# Main_circuit_SMD.net
KiCad netlist of a schematic drawn in EAGLE
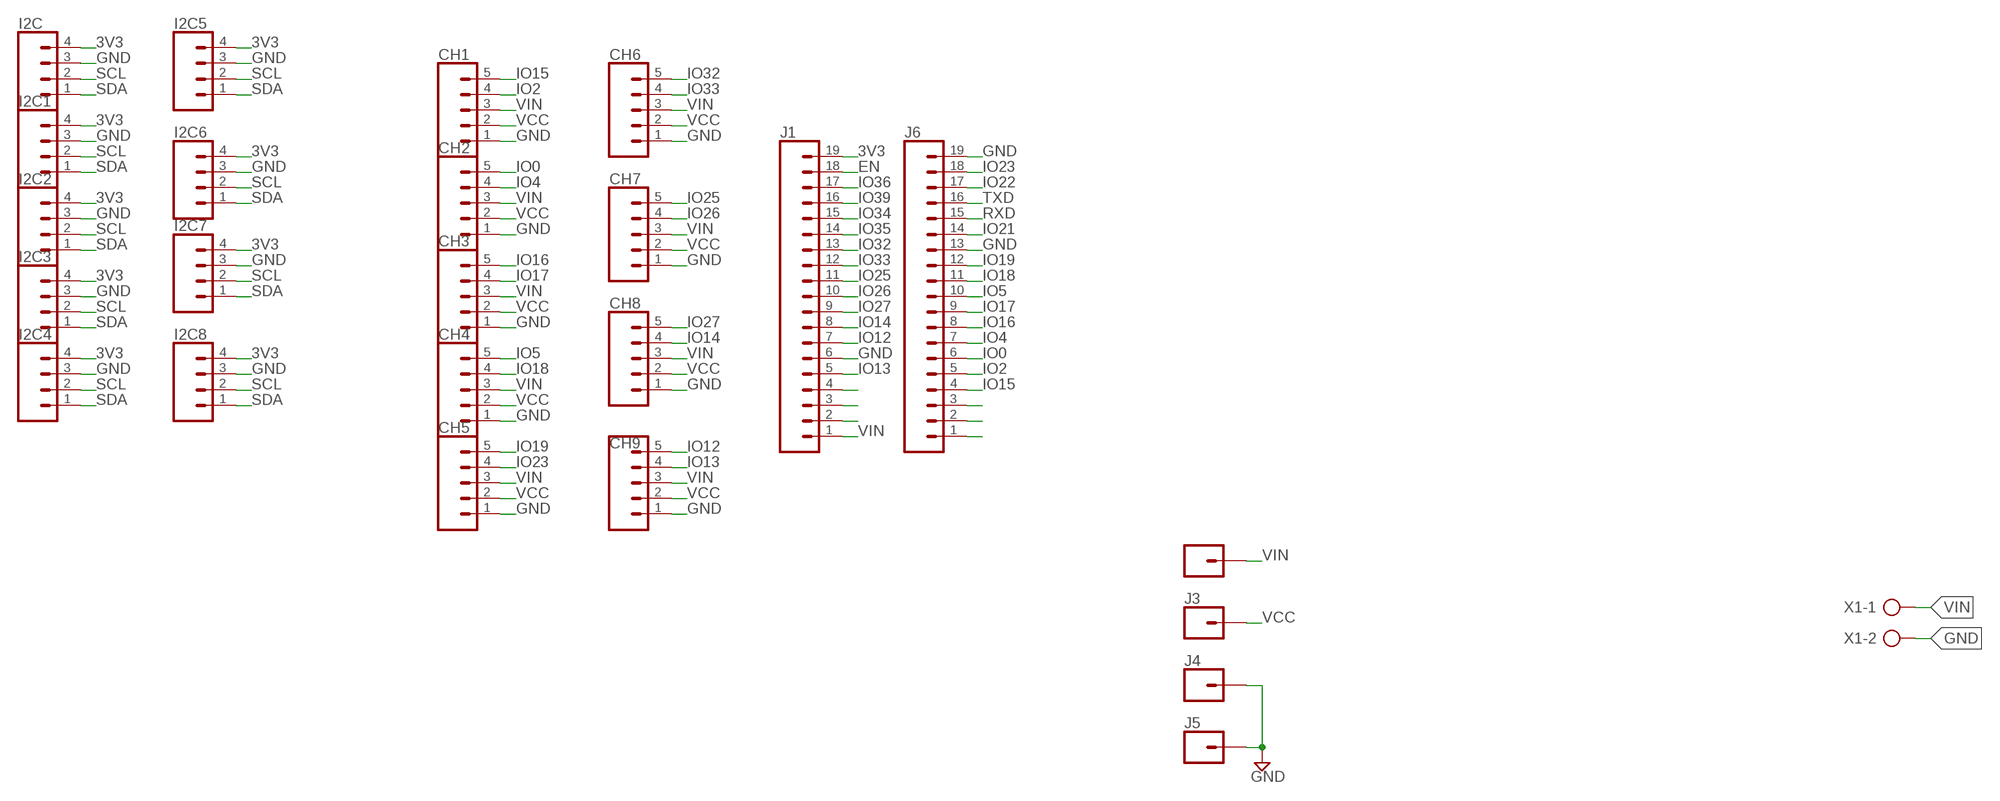
[diagram p0: schematic, sheet 1]

(export (version "E")
  (design (tool "Eeschema 10.0.6"))
  (components
    (comp (ref "CH1")
      (value "CONN_05")
      (footprint "eagle-import:1X05")
      (libsource (lib "eagle-import") (part "CONN_05"))
    )
    (comp (ref "CH2")
      (value "CONN_05")
      (footprint "eagle-import:1X05")
      (libsource (lib "eagle-import") (part "CONN_05"))
    )
    (comp (ref "CH3")
      (value "CONN_05")
      (footprint "eagle-import:1X05")
      (libsource (lib "eagle-import") (part "CONN_05"))
    )
    (comp (ref "CH4")
      (value "CONN_05")
      (footprint "eagle-import:1X05")
      (libsource (lib "eagle-import") (part "CONN_05"))
    )
    (comp (ref "CH5")
      (value "CONN_05")
      (footprint "eagle-import:1X05")
      (libsource (lib "eagle-import") (part "CONN_05"))
    )
    (comp (ref "CH6")
      (value "CONN_05")
      (footprint "eagle-import:1X05")
      (libsource (lib "eagle-import") (part "CONN_05"))
    )
    (comp (ref "CH7")
      (value "CONN_05")
      (footprint "eagle-import:1X05")
      (libsource (lib "eagle-import") (part "CONN_05"))
    )
    (comp (ref "CH8")
      (value "CONN_05")
      (footprint "eagle-import:1X05")
      (libsource (lib "eagle-import") (part "CONN_05"))
    )
    (comp (ref "CH9")
      (value "CONN_05")
      (footprint "eagle-import:1X05")
      (libsource (lib "eagle-import") (part "CONN_05"))
    )
    (comp (ref "I2C")
      (value "CONN_04")
      (footprint "eagle-import:1X04")
      (libsource (lib "eagle-import") (part "CONN_04"))
    )
    (comp (ref "I2C1")
      (value "CONN_04")
      (footprint "eagle-import:1X04")
      (libsource (lib "eagle-import") (part "CONN_04"))
    )
    (comp (ref "I2C2")
      (value "CONN_04")
      (footprint "eagle-import:1X04")
      (libsource (lib "eagle-import") (part "CONN_04"))
    )
    (comp (ref "I2C3")
      (value "CONN_04")
      (footprint "eagle-import:1X04")
      (libsource (lib "eagle-import") (part "CONN_04"))
    )
    (comp (ref "I2C4")
      (value "CONN_04")
      (footprint "eagle-import:1X04")
      (libsource (lib "eagle-import") (part "CONN_04"))
    )
    (comp (ref "I2C5")
      (value "CONN_04")
      (footprint "eagle-import:1X04")
      (libsource (lib "eagle-import") (part "CONN_04"))
    )
    (comp (ref "I2C6")
      (value "CONN_04")
      (footprint "eagle-import:1X04")
      (libsource (lib "eagle-import") (part "CONN_04"))
    )
    (comp (ref "I2C7")
      (value "CONN_04")
      (footprint "eagle-import:1X04")
      (libsource (lib "eagle-import") (part "CONN_04"))
    )
    (comp (ref "I2C8")
      (value "CONN_04")
      (footprint "eagle-import:1X04")
      (libsource (lib "eagle-import") (part "CONN_04"))
    )
    (comp (ref "J1")
      (value "CONN_19")
      (footprint "eagle-import:1X19")
      (libsource (lib "eagle-import") (part "CONN_19"))
    )
    (comp (ref "J2")
      (value "CONN_01")
      (footprint "eagle-import:1X01")
      (libsource (lib "eagle-import") (part "CONN_01"))
    )
    (comp (ref "J3")
      (value "CONN_01")
      (footprint "eagle-import:1X01")
      (libsource (lib "eagle-import") (part "CONN_01"))
    )
    (comp (ref "J4")
      (value "CONN_01")
      (footprint "eagle-import:1X01")
      (libsource (lib "eagle-import") (part "CONN_01"))
    )
    (comp (ref "J5")
      (value "CONN_01")
      (footprint "eagle-import:1X01")
      (libsource (lib "eagle-import") (part "CONN_01"))
    )
    (comp (ref "J6")
      (value "CONN_19")
      (footprint "eagle-import:1X19")
      (libsource (lib "eagle-import") (part "CONN_19"))
    )
    (comp (ref "X1")
      (value "AK500/2-H")
      (footprint "eagle-import:AK500_2-H")
      (libsource (lib "eagle-import") (part "AK500/2-H"))
    )
  )
  (nets
    (net (code "1") (name "/3V3") (class "Default")
      (node (ref "I2C") (pin "4") (pinfunction "4_4") (pintype "passive"))
      (node (ref "I2C1") (pin "4") (pinfunction "4_4") (pintype "passive"))
      (node (ref "I2C2") (pin "4") (pinfunction "4_4") (pintype "passive"))
      (node (ref "I2C3") (pin "4") (pinfunction "4_4") (pintype "passive"))
      (node (ref "I2C4") (pin "4") (pinfunction "4_4") (pintype "passive"))
      (node (ref "I2C5") (pin "4") (pinfunction "4_4") (pintype "passive"))
      (node (ref "I2C6") (pin "4") (pinfunction "4_4") (pintype "passive"))
      (node (ref "I2C7") (pin "4") (pinfunction "4_4") (pintype "passive"))
      (node (ref "I2C8") (pin "4") (pinfunction "4_4") (pintype "passive"))
      (node (ref "J1") (pin "19") (pinfunction "19_19") (pintype "passive"))
    )
    (net (code "2") (name "/EN") (class "Default")
      (node (ref "J1") (pin "18") (pinfunction "18_18") (pintype "passive"))
    )
    (net (code "3") (name "/IO0") (class "Default")
      (node (ref "CH2") (pin "5") (pinfunction "5_5") (pintype "passive"))
      (node (ref "J6") (pin "6") (pinfunction "6_6") (pintype "passive"))
    )
    (net (code "4") (name "/IO2") (class "Default")
      (node (ref "CH1") (pin "4") (pinfunction "4_4") (pintype "passive"))
      (node (ref "J6") (pin "5") (pinfunction "5_5") (pintype "passive"))
    )
    (net (code "5") (name "/IO4") (class "Default")
      (node (ref "CH2") (pin "4") (pinfunction "4_4") (pintype "passive"))
      (node (ref "J6") (pin "7") (pinfunction "7_7") (pintype "passive"))
    )
    (net (code "6") (name "/IO5") (class "Default")
      (node (ref "CH4") (pin "5") (pinfunction "5_5") (pintype "passive"))
      (node (ref "J6") (pin "10") (pinfunction "10_10") (pintype "passive"))
    )
    (net (code "7") (name "/IO12") (class "Default")
      (node (ref "CH9") (pin "5") (pinfunction "5_5") (pintype "passive"))
      (node (ref "J1") (pin "7") (pinfunction "7_7") (pintype "passive"))
    )
    (net (code "8") (name "/IO13") (class "Default")
      (node (ref "CH9") (pin "4") (pinfunction "4_4") (pintype "passive"))
      (node (ref "J1") (pin "5") (pinfunction "5_5") (pintype "passive"))
    )
    (net (code "9") (name "/IO14") (class "Default")
      (node (ref "CH8") (pin "4") (pinfunction "4_4") (pintype "passive"))
      (node (ref "J1") (pin "8") (pinfunction "8_8") (pintype "passive"))
    )
    (net (code "10") (name "/IO15") (class "Default")
      (node (ref "CH1") (pin "5") (pinfunction "5_5") (pintype "passive"))
      (node (ref "J6") (pin "4") (pinfunction "4_4") (pintype "passive"))
    )
    (net (code "11") (name "/IO16") (class "Default")
      (node (ref "CH3") (pin "5") (pinfunction "5_5") (pintype "passive"))
      (node (ref "J6") (pin "8") (pinfunction "8_8") (pintype "passive"))
    )
    (net (code "12") (name "/IO17") (class "Default")
      (node (ref "CH3") (pin "4") (pinfunction "4_4") (pintype "passive"))
      (node (ref "J6") (pin "9") (pinfunction "9_9") (pintype "passive"))
    )
    (net (code "13") (name "/IO18") (class "Default")
      (node (ref "CH4") (pin "4") (pinfunction "4_4") (pintype "passive"))
      (node (ref "J6") (pin "11") (pinfunction "11_11") (pintype "passive"))
    )
    (net (code "14") (name "/IO19") (class "Default")
      (node (ref "CH5") (pin "5") (pinfunction "5_5") (pintype "passive"))
      (node (ref "J6") (pin "12") (pinfunction "12_12") (pintype "passive"))
    )
    (net (code "15") (name "/IO21") (class "Default")
      (node (ref "J6") (pin "14") (pinfunction "14_14") (pintype "passive"))
    )
    (net (code "16") (name "/IO22") (class "Default")
      (node (ref "J6") (pin "17") (pinfunction "17_17") (pintype "passive"))
    )
    (net (code "17") (name "/IO23") (class "Default")
      (node (ref "CH5") (pin "4") (pinfunction "4_4") (pintype "passive"))
      (node (ref "J6") (pin "18") (pinfunction "18_18") (pintype "passive"))
    )
    (net (code "18") (name "/IO25") (class "Default")
      (node (ref "CH7") (pin "5") (pinfunction "5_5") (pintype "passive"))
      (node (ref "J1") (pin "11") (pinfunction "11_11") (pintype "passive"))
    )
    (net (code "19") (name "/IO26") (class "Default")
      (node (ref "CH7") (pin "4") (pinfunction "4_4") (pintype "passive"))
      (node (ref "J1") (pin "10") (pinfunction "10_10") (pintype "passive"))
    )
    (net (code "20") (name "/IO27") (class "Default")
      (node (ref "CH8") (pin "5") (pinfunction "5_5") (pintype "passive"))
      (node (ref "J1") (pin "9") (pinfunction "9_9") (pintype "passive"))
    )
    (net (code "21") (name "/IO32") (class "Default")
      (node (ref "CH6") (pin "5") (pinfunction "5_5") (pintype "passive"))
      (node (ref "J1") (pin "13") (pinfunction "13_13") (pintype "passive"))
    )
    (net (code "22") (name "/IO33") (class "Default")
      (node (ref "CH6") (pin "4") (pinfunction "4_4") (pintype "passive"))
      (node (ref "J1") (pin "12") (pinfunction "12_12") (pintype "passive"))
    )
    (net (code "23") (name "/IO34") (class "Default")
      (node (ref "J1") (pin "15") (pinfunction "15_15") (pintype "passive"))
    )
    (net (code "24") (name "/IO35") (class "Default")
      (node (ref "J1") (pin "14") (pinfunction "14_14") (pintype "passive"))
    )
    (net (code "25") (name "/IO36") (class "Default")
      (node (ref "J1") (pin "17") (pinfunction "17_17") (pintype "passive"))
    )
    (net (code "26") (name "/IO39") (class "Default")
      (node (ref "J1") (pin "16") (pinfunction "16_16") (pintype "passive"))
    )
    (net (code "27") (name "/RXD") (class "Default")
      (node (ref "J6") (pin "15") (pinfunction "15_15") (pintype "passive"))
    )
    (net (code "28") (name "/SCL") (class "Default")
      (node (ref "I2C") (pin "2") (pinfunction "2_2") (pintype "passive"))
      (node (ref "I2C1") (pin "2") (pinfunction "2_2") (pintype "passive"))
      (node (ref "I2C2") (pin "2") (pinfunction "2_2") (pintype "passive"))
      (node (ref "I2C3") (pin "2") (pinfunction "2_2") (pintype "passive"))
      (node (ref "I2C4") (pin "2") (pinfunction "2_2") (pintype "passive"))
      (node (ref "I2C5") (pin "2") (pinfunction "2_2") (pintype "passive"))
      (node (ref "I2C6") (pin "2") (pinfunction "2_2") (pintype "passive"))
      (node (ref "I2C7") (pin "2") (pinfunction "2_2") (pintype "passive"))
      (node (ref "I2C8") (pin "2") (pinfunction "2_2") (pintype "passive"))
    )
    (net (code "29") (name "/SDA") (class "Default")
      (node (ref "I2C") (pin "1") (pinfunction "1_1") (pintype "passive"))
      (node (ref "I2C1") (pin "1") (pinfunction "1_1") (pintype "passive"))
      (node (ref "I2C2") (pin "1") (pinfunction "1_1") (pintype "passive"))
      (node (ref "I2C3") (pin "1") (pinfunction "1_1") (pintype "passive"))
      (node (ref "I2C4") (pin "1") (pinfunction "1_1") (pintype "passive"))
      (node (ref "I2C5") (pin "1") (pinfunction "1_1") (pintype "passive"))
      (node (ref "I2C6") (pin "1") (pinfunction "1_1") (pintype "passive"))
      (node (ref "I2C7") (pin "1") (pinfunction "1_1") (pintype "passive"))
      (node (ref "I2C8") (pin "1") (pinfunction "1_1") (pintype "passive"))
    )
    (net (code "30") (name "/TXD") (class "Default")
      (node (ref "J6") (pin "16") (pinfunction "16_16") (pintype "passive"))
    )
    (net (code "31") (name "/VCC") (class "Default")
      (node (ref "CH1") (pin "2") (pinfunction "2_2") (pintype "passive"))
      (node (ref "CH2") (pin "2") (pinfunction "2_2") (pintype "passive"))
      (node (ref "CH3") (pin "2") (pinfunction "2_2") (pintype "passive"))
      (node (ref "CH4") (pin "2") (pinfunction "2_2") (pintype "passive"))
      (node (ref "CH5") (pin "2") (pinfunction "2_2") (pintype "passive"))
      (node (ref "CH6") (pin "2") (pinfunction "2_2") (pintype "passive"))
      (node (ref "CH7") (pin "2") (pinfunction "2_2") (pintype "passive"))
      (node (ref "CH8") (pin "2") (pinfunction "2_2") (pintype "passive"))
      (node (ref "CH9") (pin "2") (pinfunction "2_2") (pintype "passive"))
      (node (ref "J3") (pin "1") (pinfunction "1_1") (pintype "passive"))
    )
    (net (code "32") (name "GND") (class "Default")
      (node (ref "CH1") (pin "1") (pinfunction "1_1") (pintype "passive"))
      (node (ref "CH2") (pin "1") (pinfunction "1_1") (pintype "passive"))
      (node (ref "CH3") (pin "1") (pinfunction "1_1") (pintype "passive"))
      (node (ref "CH4") (pin "1") (pinfunction "1_1") (pintype "passive"))
      (node (ref "CH5") (pin "1") (pinfunction "1_1") (pintype "passive"))
      (node (ref "CH6") (pin "1") (pinfunction "1_1") (pintype "passive"))
      (node (ref "CH7") (pin "1") (pinfunction "1_1") (pintype "passive"))
      (node (ref "CH8") (pin "1") (pinfunction "1_1") (pintype "passive"))
      (node (ref "CH9") (pin "1") (pinfunction "1_1") (pintype "passive"))
      (node (ref "I2C") (pin "3") (pinfunction "3_3") (pintype "passive"))
      (node (ref "I2C1") (pin "3") (pinfunction "3_3") (pintype "passive"))
      (node (ref "I2C2") (pin "3") (pinfunction "3_3") (pintype "passive"))
      (node (ref "I2C3") (pin "3") (pinfunction "3_3") (pintype "passive"))
      (node (ref "I2C4") (pin "3") (pinfunction "3_3") (pintype "passive"))
      (node (ref "I2C5") (pin "3") (pinfunction "3_3") (pintype "passive"))
      (node (ref "I2C6") (pin "3") (pinfunction "3_3") (pintype "passive"))
      (node (ref "I2C7") (pin "3") (pinfunction "3_3") (pintype "passive"))
      (node (ref "I2C8") (pin "3") (pinfunction "3_3") (pintype "passive"))
      (node (ref "J1") (pin "6") (pinfunction "6_6") (pintype "passive"))
      (node (ref "J4") (pin "1") (pinfunction "1_1") (pintype "passive"))
      (node (ref "J5") (pin "1") (pinfunction "1_1") (pintype "passive"))
      (node (ref "J6") (pin "13") (pinfunction "13_13") (pintype "passive"))
      (node (ref "J6") (pin "19") (pinfunction "19_19") (pintype "passive"))
      (node (ref "X1") (pin "2") (pinfunction "KL_2") (pintype "passive"))
    )
    (net (code "33") (name "VIN") (class "Default")
      (node (ref "CH1") (pin "3") (pinfunction "3_3") (pintype "passive"))
      (node (ref "CH2") (pin "3") (pinfunction "3_3") (pintype "passive"))
      (node (ref "CH3") (pin "3") (pinfunction "3_3") (pintype "passive"))
      (node (ref "CH4") (pin "3") (pinfunction "3_3") (pintype "passive"))
      (node (ref "CH5") (pin "3") (pinfunction "3_3") (pintype "passive"))
      (node (ref "CH6") (pin "3") (pinfunction "3_3") (pintype "passive"))
      (node (ref "CH7") (pin "3") (pinfunction "3_3") (pintype "passive"))
      (node (ref "CH8") (pin "3") (pinfunction "3_3") (pintype "passive"))
      (node (ref "CH9") (pin "3") (pinfunction "3_3") (pintype "passive"))
      (node (ref "J1") (pin "1") (pinfunction "1_1") (pintype "passive"))
      (node (ref "J2") (pin "1") (pinfunction "1_1") (pintype "passive"))
      (node (ref "X1") (pin "1") (pinfunction "KL_1") (pintype "passive"))
    )
    (net (code "34") (name "unconnected-(J1-Pad2)") (class "Default")
      (node (ref "J1") (pin "2") (pinfunction "2_2") (pintype "passive"))
    )
    (net (code "35") (name "unconnected-(J1-Pad3)") (class "Default")
      (node (ref "J1") (pin "3") (pinfunction "3_3") (pintype "passive"))
    )
    (net (code "36") (name "unconnected-(J1-Pad4)") (class "Default")
      (node (ref "J1") (pin "4") (pinfunction "4_4") (pintype "passive"))
    )
    (net (code "37") (name "unconnected-(J6-Pad1)") (class "Default")
      (node (ref "J6") (pin "1") (pinfunction "1_1") (pintype "passive"))
    )
    (net (code "38") (name "unconnected-(J6-Pad2)") (class "Default")
      (node (ref "J6") (pin "2") (pinfunction "2_2") (pintype "passive"))
    )
    (net (code "39") (name "unconnected-(J6-Pad3)") (class "Default")
      (node (ref "J6") (pin "3") (pinfunction "3_3") (pintype "passive"))
    )
  )
)
